# automatic_battery_charger_circuit.net
KiCad netlist of a schematic drawn in EAGLE
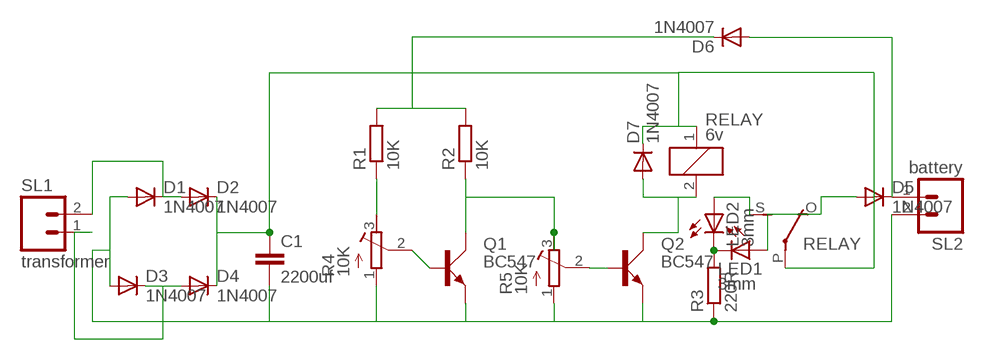
[diagram p0: schematic, sheet 1]

(export (version "E")
  (design (tool "Eeschema 10.0.6"))
  (components
    (comp (ref "C1")
      (value "2200uf")
      (footprint "eagle-import:C5B5.5")
      (libsource (lib "eagle-import") (part "C5/5.5"))
    )
    (comp (ref "D1")
      (value "1N4007")
      (footprint "eagle-import:DO41-10")
      (libsource (lib "eagle-import") (part "1N4004"))
    )
    (comp (ref "D2")
      (value "1N4007")
      (footprint "eagle-import:DO41-10")
      (libsource (lib "eagle-import") (part "1N4004"))
    )
    (comp (ref "D3")
      (value "1N4007")
      (footprint "eagle-import:DO41-10")
      (libsource (lib "eagle-import") (part "1N4004"))
    )
    (comp (ref "D4")
      (value "1N4007")
      (footprint "eagle-import:DO41-10")
      (libsource (lib "eagle-import") (part "1N4004"))
    )
    (comp (ref "D5")
      (value "1N4007")
      (footprint "eagle-import:DO41-10")
      (libsource (lib "eagle-import") (part "1N4004"))
    )
    (comp (ref "D6")
      (value "1N4007")
      (footprint "eagle-import:DO41-10")
      (libsource (lib "eagle-import") (part "1N4004"))
    )
    (comp (ref "D7")
      (value "1N4007")
      (footprint "eagle-import:DO41-10")
      (libsource (lib "eagle-import") (part "1N4004"))
    )
    (comp (ref "LED1")
      (value "3mm")
      (footprint "eagle-import:LED3MM")
      (libsource (lib "eagle-import") (part "LED3MM"))
    )
    (comp (ref "LED2")
      (value "3mm")
      (footprint "eagle-import:LED3MM")
      (libsource (lib "eagle-import") (part "LED3MM"))
    )
    (comp (ref "Q1")
      (value "BC547")
      (footprint "eagle-import:SOT54A")
      (libsource (lib "eagle-import") (part "BC547"))
    )
    (comp (ref "Q2")
      (value "BC547")
      (footprint "eagle-import:SOT54A")
      (libsource (lib "eagle-import") (part "BC547"))
    )
    (comp (ref "R1")
      (value "10K")
      (footprint "eagle-import:0204_7")
      (libsource (lib "eagle-import") (part "R-EU_0204/7"))
    )
    (comp (ref "R2")
      (value "10K")
      (footprint "eagle-import:0204_7")
      (libsource (lib "eagle-import") (part "R-EU_0204/7"))
    )
    (comp (ref "R3")
      (value "220R")
      (footprint "eagle-import:0204_7")
      (libsource (lib "eagle-import") (part "R-EU_0204/7"))
    )
    (comp (ref "R4")
      (value "10K")
      (footprint "eagle-import:RTRIM3339P")
      (libsource (lib "eagle-import") (part "R-TRIMM3339P"))
    )
    (comp (ref "R5")
      (value "10K")
      (footprint "eagle-import:RTRIM3339P")
      (libsource (lib "eagle-import") (part "R-TRIMM3339P"))
    )
    (comp (ref "RELAY")
      (value "6v")
      (footprint "eagle-import:G5LE")
      (libsource (lib "eagle-import") (part "G5LE"))
    )
    (comp (ref "SL1")
      (value "transformer")
      (footprint "eagle-import:02P")
      (libsource (lib "eagle-import") (part "M02"))
    )
    (comp (ref "SL2")
      (value "battery")
      (footprint "eagle-import:02P")
      (libsource (lib "eagle-import") (part "M02"))
    )
  )
  (nets
    (net (code "1") (name "Net-(C1-Pad1)") (class "Default")
      (node (ref "C1") (pin "1") (pinfunction "1_1") (pintype "passive"))
      (node (ref "D2") (pin "C") (pinfunction "C_C") (pintype "passive"))
      (node (ref "D4") (pin "C") (pinfunction "C_C") (pintype "passive"))
      (node (ref "D7") (pin "C") (pinfunction "C_C") (pintype "passive"))
      (node (ref "RELAY") (pin "1") (pinfunction "1_1") (pintype "passive"))
      (node (ref "RELAY") (pin "P") (pinfunction "P_P") (pintype "passive"))
    )
    (net (code "2") (name "Net-(D1-PadC)") (class "Default")
      (node (ref "D1") (pin "C") (pinfunction "C_C") (pintype "passive"))
      (node (ref "D2") (pin "A") (pinfunction "A_A") (pintype "passive"))
      (node (ref "SL1") (pin "2") (pinfunction "2_2") (pintype "passive"))
    )
    (net (code "3") (name "Net-(D3-PadC)") (class "Default")
      (node (ref "D3") (pin "C") (pinfunction "C_C") (pintype "passive"))
      (node (ref "D4") (pin "A") (pinfunction "A_A") (pintype "passive"))
      (node (ref "SL1") (pin "1") (pinfunction "1_1") (pintype "passive"))
    )
    (net (code "4") (name "Net-(D5-PadA)") (class "Default")
      (node (ref "D5") (pin "A") (pinfunction "A_A") (pintype "passive"))
      (node (ref "LED1") (pin "A") (pinfunction "A_A") (pintype "passive"))
      (node (ref "RELAY") (pin "O") (pinfunction "O_O") (pintype "passive"))
    )
    (net (code "5") (name "Net-(D5-PadC)") (class "Default")
      (node (ref "D5") (pin "C") (pinfunction "C_C") (pintype "passive"))
      (node (ref "D6") (pin "A") (pinfunction "A_A") (pintype "passive"))
      (node (ref "SL2") (pin "1") (pinfunction "1_1") (pintype "passive"))
    )
    (net (code "6") (name "Net-(D6-PadC)") (class "Default")
      (node (ref "D6") (pin "C") (pinfunction "C_C") (pintype "passive"))
      (node (ref "R1") (pin "2") (pinfunction "2_2") (pintype "passive"))
      (node (ref "R2") (pin "2") (pinfunction "2_2") (pintype "passive"))
    )
    (net (code "7") (name "Net-(D7-PadA)") (class "Default")
      (node (ref "D7") (pin "A") (pinfunction "A_A") (pintype "passive"))
      (node (ref "Q2") (pin "C") (pinfunction "C_C") (pintype "passive"))
      (node (ref "RELAY") (pin "2") (pinfunction "2_2") (pintype "passive"))
    )
    (net (code "8") (name "Net-(LED1-C)") (class "Default")
      (node (ref "LED1") (pin "K") (pinfunction "C_K") (pintype "passive"))
      (node (ref "LED2") (pin "K") (pinfunction "C_K") (pintype "passive"))
      (node (ref "R3") (pin "2") (pinfunction "2_2") (pintype "passive"))
    )
    (net (code "9") (name "Net-(LED2-PadA)") (class "Default")
      (node (ref "LED2") (pin "A") (pinfunction "A_A") (pintype "passive"))
      (node (ref "RELAY") (pin "S") (pinfunction "S_S") (pintype "passive"))
    )
    (net (code "10") (name "Net-(R4-A)") (class "Default")
      (node (ref "C1") (pin "2") (pinfunction "2_2") (pintype "passive"))
      (node (ref "D1") (pin "A") (pinfunction "A_A") (pintype "passive"))
      (node (ref "D3") (pin "A") (pinfunction "A_A") (pintype "passive"))
      (node (ref "Q1") (pin "E") (pinfunction "E_E") (pintype "passive"))
      (node (ref "Q2") (pin "E") (pinfunction "E_E") (pintype "passive"))
      (node (ref "R3") (pin "1") (pinfunction "1_1") (pintype "passive"))
      (node (ref "R4") (pin "1") (pinfunction "A_1") (pintype "passive"))
      (node (ref "R5") (pin "1") (pinfunction "A_1") (pintype "passive"))
      (node (ref "SL2") (pin "2") (pinfunction "2_2") (pintype "passive"))
    )
    (net (code "11") (name "Net-(R4-E)") (class "Default")
      (node (ref "R1") (pin "1") (pinfunction "1_1") (pintype "passive"))
      (node (ref "R4") (pin "3") (pinfunction "E_3") (pintype "passive"))
    )
    (net (code "12") (name "Net-(R4-S)") (class "Default")
      (node (ref "Q1") (pin "B") (pinfunction "B_B") (pintype "passive"))
      (node (ref "R4") (pin "2") (pinfunction "S_2") (pintype "passive"))
    )
    (net (code "13") (name "Net-(R5-E)") (class "Default")
      (node (ref "Q1") (pin "C") (pinfunction "C_C") (pintype "passive"))
      (node (ref "R2") (pin "1") (pinfunction "1_1") (pintype "passive"))
      (node (ref "R5") (pin "3") (pinfunction "E_3") (pintype "passive"))
    )
    (net (code "14") (name "Net-(R5-S)") (class "Default")
      (node (ref "Q2") (pin "B") (pinfunction "B_B") (pintype "passive"))
      (node (ref "R5") (pin "2") (pinfunction "S_2") (pintype "passive"))
    )
  )
)
